# hft.net
KiCad netlist of a schematic drawn in EAGLE
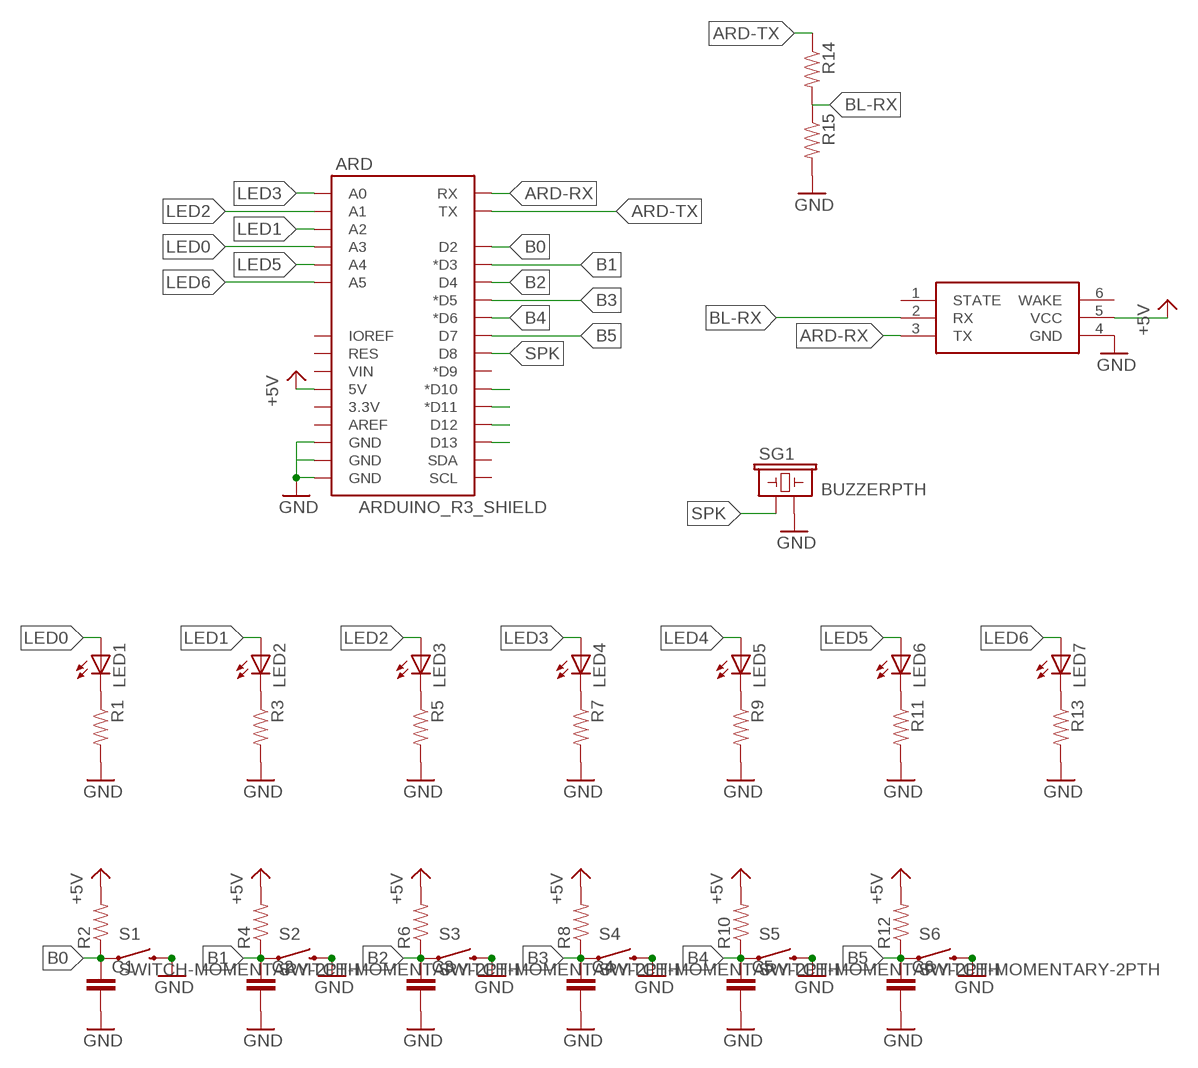
[diagram p0: schematic, sheet 1]

(export (version "E")
  (design (tool "Eeschema 10.0.6"))
  (components
    (comp (ref "ARD")
      (value "ARDUINO_R3_SHIELD")
      (footprint "eagle-import:UNO_R3_SHIELD")
      (libsource (lib "eagle-import") (part "ARDUINO_R3_SHIELD"))
    )
    (comp (ref "C1")
      (value "CAPACITOR0603-CAP")
      (footprint "eagle-import:0603-CAP")
      (libsource (lib "eagle-import") (part "CAPACITOR0603-CAP"))
    )
    (comp (ref "C2")
      (value "CAPACITOR0603-CAP")
      (footprint "eagle-import:0603-CAP")
      (libsource (lib "eagle-import") (part "CAPACITOR0603-CAP"))
    )
    (comp (ref "C3")
      (value "CAPACITOR0603-CAP")
      (footprint "eagle-import:0603-CAP")
      (libsource (lib "eagle-import") (part "CAPACITOR0603-CAP"))
    )
    (comp (ref "C4")
      (value "CAPACITOR0603-CAP")
      (footprint "eagle-import:0603-CAP")
      (libsource (lib "eagle-import") (part "CAPACITOR0603-CAP"))
    )
    (comp (ref "C5")
      (value "CAPACITOR0603-CAP")
      (footprint "eagle-import:0603-CAP")
      (libsource (lib "eagle-import") (part "CAPACITOR0603-CAP"))
    )
    (comp (ref "C6")
      (value "CAPACITOR0603-CAP")
      (footprint "eagle-import:0603-CAP")
      (libsource (lib "eagle-import") (part "CAPACITOR0603-CAP"))
    )
    (comp (ref "LED1")
      (value "LED5MM")
      (footprint "eagle-import:LED5MM")
      (libsource (lib "eagle-import") (part "LED5MM"))
    )
    (comp (ref "LED2")
      (value "LED5MM")
      (footprint "eagle-import:LED5MM")
      (libsource (lib "eagle-import") (part "LED5MM"))
    )
    (comp (ref "LED3")
      (value "LED5MM")
      (footprint "eagle-import:LED5MM")
      (libsource (lib "eagle-import") (part "LED5MM"))
    )
    (comp (ref "LED4")
      (value "LED5MM")
      (footprint "eagle-import:LED5MM")
      (libsource (lib "eagle-import") (part "LED5MM"))
    )
    (comp (ref "LED5")
      (value "LED5MM")
      (footprint "eagle-import:LED5MM")
      (libsource (lib "eagle-import") (part "LED5MM"))
    )
    (comp (ref "LED6")
      (value "LED5MM")
      (footprint "eagle-import:LED5MM")
      (libsource (lib "eagle-import") (part "LED5MM"))
    )
    (comp (ref "LED7")
      (value "LED5MM")
      (footprint "eagle-import:LED5MM")
      (libsource (lib "eagle-import") (part "LED5MM"))
    )
    (comp (ref "R1")
      (value "RESISTOR")
      (footprint "eagle-import:0603-RES")
      (libsource (lib "eagle-import") (part "RESISTOR"))
    )
    (comp (ref "R2")
      (value "RESISTOR")
      (footprint "eagle-import:0603-RES")
      (libsource (lib "eagle-import") (part "RESISTOR"))
    )
    (comp (ref "R3")
      (value "RESISTOR")
      (footprint "eagle-import:0603-RES")
      (libsource (lib "eagle-import") (part "RESISTOR"))
    )
    (comp (ref "R4")
      (value "RESISTOR")
      (footprint "eagle-import:0603-RES")
      (libsource (lib "eagle-import") (part "RESISTOR"))
    )
    (comp (ref "R5")
      (value "RESISTOR")
      (footprint "eagle-import:0603-RES")
      (libsource (lib "eagle-import") (part "RESISTOR"))
    )
    (comp (ref "R6")
      (value "RESISTOR")
      (footprint "eagle-import:0603-RES")
      (libsource (lib "eagle-import") (part "RESISTOR"))
    )
    (comp (ref "R7")
      (value "RESISTOR")
      (footprint "eagle-import:0603-RES")
      (libsource (lib "eagle-import") (part "RESISTOR"))
    )
    (comp (ref "R8")
      (value "RESISTOR")
      (footprint "eagle-import:0603-RES")
      (libsource (lib "eagle-import") (part "RESISTOR"))
    )
    (comp (ref "R9")
      (value "RESISTOR")
      (footprint "eagle-import:0603-RES")
      (libsource (lib "eagle-import") (part "RESISTOR"))
    )
    (comp (ref "R10")
      (value "RESISTOR")
      (footprint "eagle-import:0603-RES")
      (libsource (lib "eagle-import") (part "RESISTOR"))
    )
    (comp (ref "R11")
      (value "RESISTOR")
      (footprint "eagle-import:0603-RES")
      (libsource (lib "eagle-import") (part "RESISTOR"))
    )
    (comp (ref "R12")
      (value "RESISTOR")
      (footprint "eagle-import:0603-RES")
      (libsource (lib "eagle-import") (part "RESISTOR"))
    )
    (comp (ref "R13")
      (value "RESISTOR")
      (footprint "eagle-import:0603-RES")
      (libsource (lib "eagle-import") (part "RESISTOR"))
    )
    (comp (ref "R14")
      (value "RESISTOR")
      (footprint "eagle-import:0603-RES")
      (libsource (lib "eagle-import") (part "RESISTOR"))
    )
    (comp (ref "R15")
      (value "RESISTOR")
      (footprint "eagle-import:0603-RES")
      (libsource (lib "eagle-import") (part "RESISTOR"))
    )
    (comp (ref "S1")
      (value "SWITCH-MOMENTARY-2PTH")
      (footprint "eagle-import:TACTILE-PTH")
      (libsource (lib "eagle-import") (part "SWITCH-MOMENTARY-2PTH"))
    )
    (comp (ref "S2")
      (value "SWITCH-MOMENTARY-2PTH")
      (footprint "eagle-import:TACTILE-PTH")
      (libsource (lib "eagle-import") (part "SWITCH-MOMENTARY-2PTH"))
    )
    (comp (ref "S3")
      (value "SWITCH-MOMENTARY-2PTH")
      (footprint "eagle-import:TACTILE-PTH")
      (libsource (lib "eagle-import") (part "SWITCH-MOMENTARY-2PTH"))
    )
    (comp (ref "S4")
      (value "SWITCH-MOMENTARY-2PTH")
      (footprint "eagle-import:TACTILE-PTH")
      (libsource (lib "eagle-import") (part "SWITCH-MOMENTARY-2PTH"))
    )
    (comp (ref "S5")
      (value "SWITCH-MOMENTARY-2PTH")
      (footprint "eagle-import:TACTILE-PTH")
      (libsource (lib "eagle-import") (part "SWITCH-MOMENTARY-2PTH"))
    )
    (comp (ref "S6")
      (value "SWITCH-MOMENTARY-2PTH")
      (footprint "eagle-import:TACTILE-PTH")
      (libsource (lib "eagle-import") (part "SWITCH-MOMENTARY-2PTH"))
    )
    (comp (ref "SG1")
      (value "BUZZERPTH")
      (footprint "eagle-import:BUZZER-12MM")
      (libsource (lib "eagle-import") (part "BUZZERPTH"))
    )
    (comp (ref "U$8")
      (value "HC-06")
      (footprint "eagle-import:HC-06_BREAKOUT")
      (libsource (lib "eagle-import") (part "HC-06"))
    )
  )
  (nets
    (net (code "1") (name "+5V") (class "Default")
      (node (ref "ARD") (pin "5V") (pinfunction "5V_5V") (pintype "bidirectional"))
      (node (ref "R10") (pin "2") (pinfunction "2_2") (pintype "passive"))
      (node (ref "R12") (pin "2") (pinfunction "2_2") (pintype "passive"))
      (node (ref "R2") (pin "2") (pinfunction "2_2") (pintype "passive"))
      (node (ref "R4") (pin "2") (pinfunction "2_2") (pintype "passive"))
      (node (ref "R6") (pin "2") (pinfunction "2_2") (pintype "passive"))
      (node (ref "R8") (pin "2") (pinfunction "2_2") (pintype "passive"))
      (node (ref "U$8") (pin "5") (pinfunction "VCC_5") (pintype "bidirectional"))
    )
    (net (code "2") (name "ARD-RX") (class "Default")
      (node (ref "ARD") (pin "RX") (pinfunction "RX_RX") (pintype "bidirectional"))
      (node (ref "U$8") (pin "3") (pinfunction "TX_3") (pintype "bidirectional"))
    )
    (net (code "3") (name "ARD-TX") (class "Default")
      (node (ref "ARD") (pin "TX") (pinfunction "TX_TX") (pintype "bidirectional"))
      (node (ref "R14") (pin "1") (pinfunction "1_1") (pintype "passive"))
    )
    (net (code "4") (name "B0") (class "Default")
      (node (ref "ARD") (pin "D2") (pinfunction "D2_D2") (pintype "bidirectional"))
      (node (ref "C1") (pin "1") (pinfunction "1_1") (pintype "passive"))
      (node (ref "R2") (pin "1") (pinfunction "1_1") (pintype "passive"))
      (node (ref "S1") (pin "1") (pinfunction "1_1") (pintype "passive"))
    )
    (net (code "5") (name "B1") (class "Default")
      (node (ref "ARD") (pin "D3") (pinfunction "*D3_D3") (pintype "bidirectional"))
      (node (ref "C2") (pin "1") (pinfunction "1_1") (pintype "passive"))
      (node (ref "R4") (pin "1") (pinfunction "1_1") (pintype "passive"))
      (node (ref "S2") (pin "1") (pinfunction "1_1") (pintype "passive"))
    )
    (net (code "6") (name "B2") (class "Default")
      (node (ref "ARD") (pin "D4") (pinfunction "D4_D4") (pintype "bidirectional"))
      (node (ref "C3") (pin "1") (pinfunction "1_1") (pintype "passive"))
      (node (ref "R6") (pin "1") (pinfunction "1_1") (pintype "passive"))
      (node (ref "S3") (pin "1") (pinfunction "1_1") (pintype "passive"))
    )
    (net (code "7") (name "B3") (class "Default")
      (node (ref "ARD") (pin "D5") (pinfunction "*D5_D5") (pintype "bidirectional"))
      (node (ref "C4") (pin "1") (pinfunction "1_1") (pintype "passive"))
      (node (ref "R8") (pin "1") (pinfunction "1_1") (pintype "passive"))
      (node (ref "S4") (pin "1") (pinfunction "1_1") (pintype "passive"))
    )
    (net (code "8") (name "B4") (class "Default")
      (node (ref "ARD") (pin "D6") (pinfunction "*D6_D6") (pintype "bidirectional"))
      (node (ref "C5") (pin "1") (pinfunction "1_1") (pintype "passive"))
      (node (ref "R10") (pin "1") (pinfunction "1_1") (pintype "passive"))
      (node (ref "S5") (pin "1") (pinfunction "1_1") (pintype "passive"))
    )
    (net (code "9") (name "B5") (class "Default")
      (node (ref "ARD") (pin "D7") (pinfunction "D7_D7") (pintype "bidirectional"))
      (node (ref "C6") (pin "1") (pinfunction "1_1") (pintype "passive"))
      (node (ref "R12") (pin "1") (pinfunction "1_1") (pintype "passive"))
      (node (ref "S6") (pin "1") (pinfunction "1_1") (pintype "passive"))
    )
    (net (code "10") (name "BL-RX") (class "Default")
      (node (ref "R14") (pin "2") (pinfunction "2_2") (pintype "passive"))
      (node (ref "R15") (pin "1") (pinfunction "1_1") (pintype "passive"))
      (node (ref "U$8") (pin "2") (pinfunction "RX_2") (pintype "bidirectional"))
    )
    (net (code "11") (name "GND") (class "Default")
      (node (ref "ARD") (pin "GND@0") (pinfunction "GND_GND@0") (pintype "bidirectional"))
      (node (ref "ARD") (pin "GND@1") (pinfunction "GND_GND@1") (pintype "bidirectional"))
      (node (ref "ARD") (pin "GND@2") (pinfunction "GND_GND@2") (pintype "bidirectional"))
      (node (ref "C1") (pin "2") (pinfunction "2_2") (pintype "passive"))
      (node (ref "C2") (pin "2") (pinfunction "2_2") (pintype "passive"))
      (node (ref "C3") (pin "2") (pinfunction "2_2") (pintype "passive"))
      (node (ref "C4") (pin "2") (pinfunction "2_2") (pintype "passive"))
      (node (ref "C5") (pin "2") (pinfunction "2_2") (pintype "passive"))
      (node (ref "C6") (pin "2") (pinfunction "2_2") (pintype "passive"))
      (node (ref "R1") (pin "2") (pinfunction "2_2") (pintype "passive"))
      (node (ref "R11") (pin "2") (pinfunction "2_2") (pintype "passive"))
      (node (ref "R13") (pin "2") (pinfunction "2_2") (pintype "passive"))
      (node (ref "R15") (pin "2") (pinfunction "2_2") (pintype "passive"))
      (node (ref "R3") (pin "2") (pinfunction "2_2") (pintype "passive"))
      (node (ref "R5") (pin "2") (pinfunction "2_2") (pintype "passive"))
      (node (ref "R7") (pin "2") (pinfunction "2_2") (pintype "passive"))
      (node (ref "R9") (pin "2") (pinfunction "2_2") (pintype "passive"))
      (node (ref "S1") (pin "3") (pinfunction "2_3") (pintype "passive"))
      (node (ref "S2") (pin "3") (pinfunction "2_3") (pintype "passive"))
      (node (ref "S3") (pin "3") (pinfunction "2_3") (pintype "passive"))
      (node (ref "S4") (pin "3") (pinfunction "2_3") (pintype "passive"))
      (node (ref "S5") (pin "3") (pinfunction "2_3") (pintype "passive"))
      (node (ref "S6") (pin "3") (pinfunction "2_3") (pintype "passive"))
      (node (ref "SG1") (pin "-") (pinfunction "2_-") (pintype "passive"))
      (node (ref "U$8") (pin "4") (pinfunction "GND_4") (pintype "bidirectional"))
    )
    (net (code "12") (name "LED0") (class "Default")
      (node (ref "ARD") (pin "A3") (pinfunction "A3_A3") (pintype "bidirectional"))
      (node (ref "LED1") (pin "A") (pinfunction "A_A") (pintype "passive"))
    )
    (net (code "13") (name "LED1") (class "Default")
      (node (ref "ARD") (pin "A2") (pinfunction "A2_A2") (pintype "bidirectional"))
      (node (ref "LED2") (pin "A") (pinfunction "A_A") (pintype "passive"))
    )
    (net (code "14") (name "LED2") (class "Default")
      (node (ref "ARD") (pin "A1") (pinfunction "A1_A1") (pintype "bidirectional"))
      (node (ref "LED3") (pin "A") (pinfunction "A_A") (pintype "passive"))
    )
    (net (code "15") (name "LED3") (class "Default")
      (node (ref "ARD") (pin "A0") (pinfunction "A0_A0") (pintype "bidirectional"))
      (node (ref "LED4") (pin "A") (pinfunction "A_A") (pintype "passive"))
    )
    (net (code "16") (name "LED4") (class "Default")
      (node (ref "LED5") (pin "A") (pinfunction "A_A") (pintype "passive"))
    )
    (net (code "17") (name "LED5") (class "Default")
      (node (ref "ARD") (pin "A4") (pinfunction "A4_A4") (pintype "bidirectional"))
      (node (ref "LED6") (pin "A") (pinfunction "A_A") (pintype "passive"))
    )
    (net (code "18") (name "LED6") (class "Default")
      (node (ref "ARD") (pin "A5") (pinfunction "A5_A5") (pintype "bidirectional"))
      (node (ref "LED7") (pin "A") (pinfunction "A_A") (pintype "passive"))
    )
    (net (code "19") (name "Net-(LED1-C)") (class "Default")
      (node (ref "LED1") (pin "K") (pinfunction "C_K") (pintype "passive"))
      (node (ref "R1") (pin "1") (pinfunction "1_1") (pintype "passive"))
    )
    (net (code "20") (name "Net-(LED2-C)") (class "Default")
      (node (ref "LED2") (pin "K") (pinfunction "C_K") (pintype "passive"))
      (node (ref "R3") (pin "1") (pinfunction "1_1") (pintype "passive"))
    )
    (net (code "21") (name "Net-(LED3-C)") (class "Default")
      (node (ref "LED3") (pin "K") (pinfunction "C_K") (pintype "passive"))
      (node (ref "R5") (pin "1") (pinfunction "1_1") (pintype "passive"))
    )
    (net (code "22") (name "Net-(LED4-C)") (class "Default")
      (node (ref "LED4") (pin "K") (pinfunction "C_K") (pintype "passive"))
      (node (ref "R7") (pin "1") (pinfunction "1_1") (pintype "passive"))
    )
    (net (code "23") (name "Net-(LED5-C)") (class "Default")
      (node (ref "LED5") (pin "K") (pinfunction "C_K") (pintype "passive"))
      (node (ref "R9") (pin "1") (pinfunction "1_1") (pintype "passive"))
    )
    (net (code "24") (name "Net-(LED6-C)") (class "Default")
      (node (ref "LED6") (pin "K") (pinfunction "C_K") (pintype "passive"))
      (node (ref "R11") (pin "1") (pinfunction "1_1") (pintype "passive"))
    )
    (net (code "25") (name "Net-(LED7-C)") (class "Default")
      (node (ref "LED7") (pin "K") (pinfunction "C_K") (pintype "passive"))
      (node (ref "R13") (pin "1") (pinfunction "1_1") (pintype "passive"))
    )
    (net (code "26") (name "SPK") (class "Default")
      (node (ref "ARD") (pin "D8") (pinfunction "D8_D8") (pintype "bidirectional"))
      (node (ref "SG1") (pin "+") (pinfunction "1_+") (pintype "passive"))
    )
    (net (code "27") (name "unconnected-(ARD-*D9-PadD9)") (class "Default")
      (node (ref "ARD") (pin "D9") (pinfunction "*D9_D9") (pintype "bidirectional"))
    )
    (net (code "28") (name "unconnected-(ARD-*D10-PadD10)") (class "Default")
      (node (ref "ARD") (pin "D10") (pinfunction "*D10_D10") (pintype "bidirectional"))
    )
    (net (code "29") (name "unconnected-(ARD-*D11-PadD11)") (class "Default")
      (node (ref "ARD") (pin "D11") (pinfunction "*D11_D11") (pintype "bidirectional"))
    )
    (net (code "30") (name "unconnected-(ARD-Pad3.3V)") (class "Default")
      (node (ref "ARD") (pin "3.3V") (pinfunction "3.3V_3.3V") (pintype "bidirectional"))
    )
    (net (code "31") (name "unconnected-(ARD-PadAREF)") (class "Default")
      (node (ref "ARD") (pin "AREF") (pinfunction "AREF_AREF") (pintype "bidirectional"))
    )
    (net (code "32") (name "unconnected-(ARD-PadD12)") (class "Default")
      (node (ref "ARD") (pin "D12") (pinfunction "D12_D12") (pintype "bidirectional"))
    )
    (net (code "33") (name "unconnected-(ARD-PadD13)") (class "Default")
      (node (ref "ARD") (pin "D13") (pinfunction "D13_D13") (pintype "bidirectional"))
    )
    (net (code "34") (name "unconnected-(ARD-PadIOREF)") (class "Default")
      (node (ref "ARD") (pin "IOREF") (pinfunction "IOREF_IOREF") (pintype "bidirectional"))
    )
    (net (code "35") (name "unconnected-(ARD-PadRES)") (class "Default")
      (node (ref "ARD") (pin "RES") (pinfunction "RES_RES") (pintype "bidirectional"))
    )
    (net (code "36") (name "unconnected-(ARD-PadSCL)") (class "Default")
      (node (ref "ARD") (pin "SCL") (pinfunction "SCL_SCL") (pintype "bidirectional"))
    )
    (net (code "37") (name "unconnected-(ARD-PadSDA)") (class "Default")
      (node (ref "ARD") (pin "SDA") (pinfunction "SDA_SDA") (pintype "bidirectional"))
    )
    (net (code "38") (name "unconnected-(ARD-PadVIN)") (class "Default")
      (node (ref "ARD") (pin "VIN") (pinfunction "VIN_VIN") (pintype "bidirectional"))
    )
    (net (code "39") (name "unconnected-(U$8-STATE-Pad1)") (class "Default")
      (node (ref "U$8") (pin "1") (pinfunction "STATE_1") (pintype "bidirectional"))
    )
    (net (code "40") (name "unconnected-(U$8-WAKE-Pad6)") (class "Default")
      (node (ref "U$8") (pin "6") (pinfunction "WAKE_6") (pintype "bidirectional"))
    )
  )
)
